# ir.net
KiCad netlist of a schematic drawn in Altium Designer
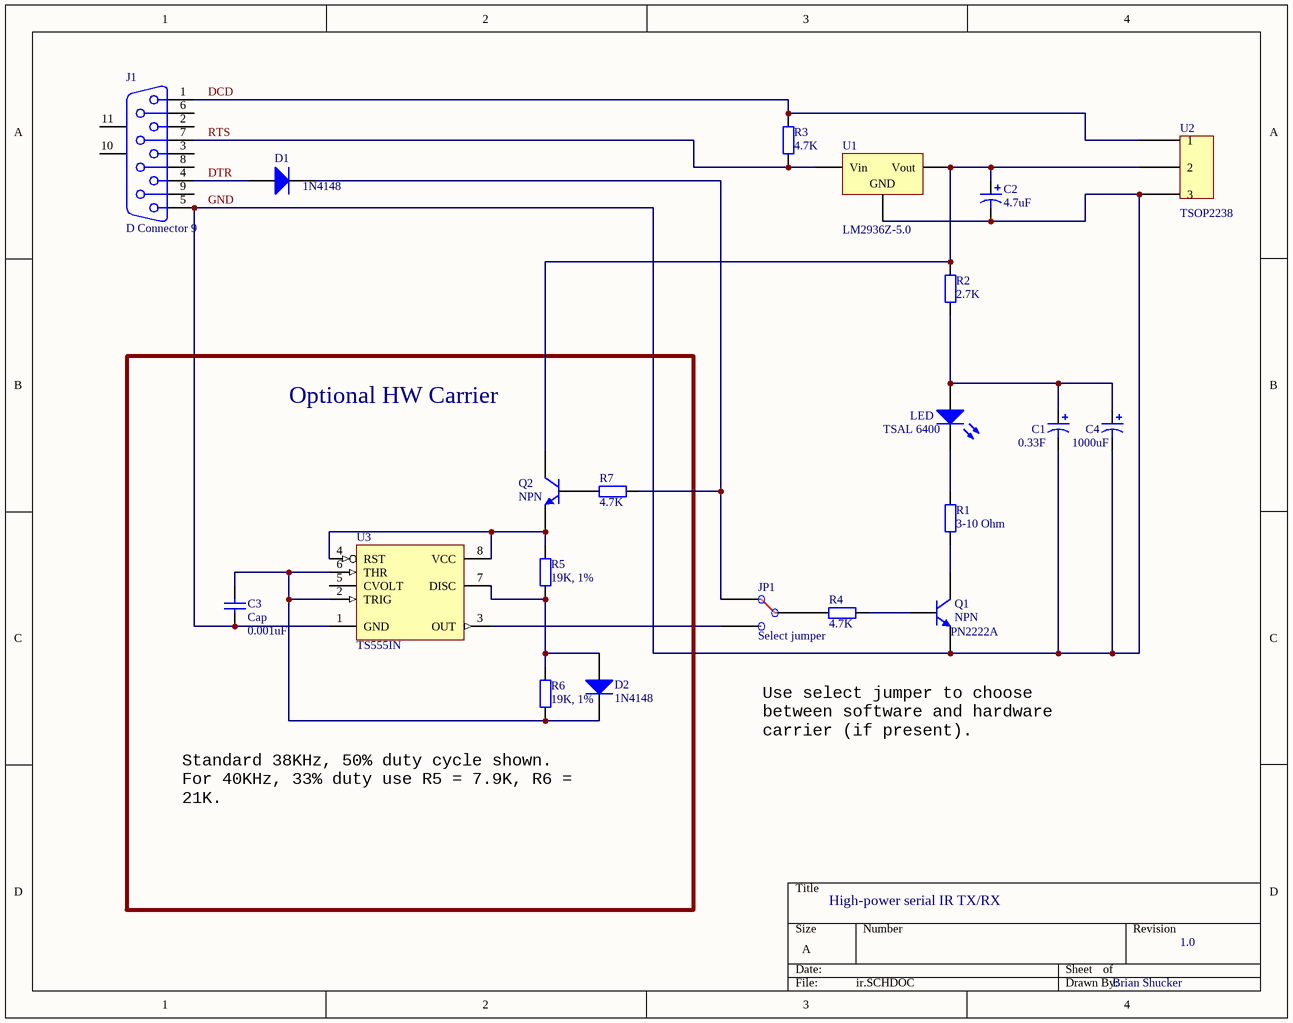
[diagram p0: ir.SCHDOC]

(export (version "E")
  (design (tool "Eeschema 10.0.6"))
  (components
    (comp (ref "C1")
      (value "0.33F")
      (footprint "SuperCapacitor")
      (description "Polarized Capacitor (Radial)")
      (fields (field (name "PUBLISHER") "Altium Limited"))
      (libsource (lib "Miscellaneous Devices") (part "Cap Pol1"))
    )
    (comp (ref "C2")
      (value "4.7uF")
      (footprint "CAPPR1.5-4x5")
      (description "Polarized Capacitor (Radial)")
      (fields (field (name "Comment") "Cap Pol1") (field (name "PUBLISHER") "Altium Limited"))
      (libsource (lib "Miscellaneous Devices") (part "Cap Pol1"))
    )
    (comp (ref "C3")
      (value "Cap")
      (footprint "Axial-0.1")
      (description "Capacitor")
      (fields (field (name "ALTIUM_VALUE") "0.001uF") (field (name "PUBLISHER") "Altium Limited"))
      (libsource (lib "Miscellaneous Devices") (part "Cap"))
    )
    (comp (ref "C4")
      (value "1000uF")
      (footprint "Cap 10mm (5mm lead space)")
      (description "Polarized Capacitor (Radial)")
      (fields (field (name "PUBLISHER") "Altium Limited"))
      (libsource (lib "Miscellaneous Devices") (part "Cap Pol1"))
    )
    (comp (ref "D1")
      (value "1N4148")
      (footprint "DIO7.1-3.9x1.9")
      (description "High Conductance Fast Diode")
      (fields (field (name "PUBLISHER") "Altium Limited"))
      (libsource (lib "Miscellaneous Devices") (part "Diode 1N4148"))
    )
    (comp (ref "D2")
      (value "1N4148")
      (footprint "DIO7.1-3.9x1.9")
      (description "High Conductance Fast Diode")
      (fields (field (name "PUBLISHER") "Altium Limited"))
      (libsource (lib "Miscellaneous Devices") (part "Diode 1N4148"))
    )
    (comp (ref "J1")
      (value "D Connector 9")
      (footprint "DSUB1.385-2H9")
      (description "Receptacle Assembly, 9 Position, Right Angle")
      (fields (field (name "PUBLISHER") "Altium Limited"))
      (libsource (lib "Miscellaneous Connectors") (part "D Connector 9"))
    )
    (comp (ref "JP1")
      (value "Select jumper")
      (footprint "Select Jumper")
      (description "Jumper switch: 1 common, 2 poles")
      (libsource (lib "robo") (part "Select jumper"))
    )
    (comp (ref "LED")
      (value "TSAL 6400")
      (footprint "LED")
      (description "Typical INFRARED GaAs LED")
      (fields (field (name "PUBLISHER") "Altium Limited"))
      (libsource (lib "Miscellaneous Devices") (part "LED0"))
    )
    (comp (ref "Q1")
      (value "NPN")
      (footprint "TO-92")
      (description "NPN Bipolar Transistor")
      (fields (field (name "PUBLISHER") "Altium Limited"))
      (libsource (lib "Miscellaneous Devices") (part "NPN"))
    )
    (comp (ref "Q2")
      (value "NPN")
      (footprint "TO-92")
      (description "NPN Bipolar Transistor")
      (fields (field (name "PUBLISHER") "Altium Limited"))
      (libsource (lib "Miscellaneous Devices") (part "NPN"))
    )
    (comp (ref "R1")
      (value "3-10 Ohm")
      (footprint "AXIAL-0.5")
      (description "Resistor")
      (fields (field (name "PUBLISHER") "Altium Limited"))
      (libsource (lib "") (part "Res2_1"))
    )
    (comp (ref "R2")
      (value "2.7K")
      (footprint "AXIAL-0.4")
      (description "Resistor")
      (fields (field (name "PUBLISHER") "Altium Limited"))
      (libsource (lib "") (part "Res2_1"))
    )
    (comp (ref "R3")
      (value "4.7K")
      (footprint "AXIAL-0.4")
      (description "Resistor")
      (fields (field (name "PUBLISHER") "Altium Limited"))
      (libsource (lib "") (part "Res2_1"))
    )
    (comp (ref "R4")
      (value "4.7K")
      (footprint "AXIAL-0.4")
      (description "Resistor")
      (fields (field (name "Comment") "Res2") (field (name "PUBLISHER") "Altium Limited"))
      (libsource (lib "Miscellaneous Devices") (part "Res2"))
    )
    (comp (ref "R5")
      (value "19K, 1%")
      (footprint "AXIAL-0.4")
      (description "Resistor")
      (fields (field (name "Comment") "Res2") (field (name "PUBLISHER") "Altium Limited"))
      (libsource (lib "") (part "Res2_1"))
    )
    (comp (ref "R6")
      (value "19K, 1%")
      (footprint "AXIAL-0.4")
      (description "Resistor")
      (fields (field (name "Comment") "Res2") (field (name "PUBLISHER") "Altium Limited"))
      (libsource (lib "") (part "Res2_1"))
    )
    (comp (ref "R7")
      (value "4.7K")
      (footprint "AXIAL-0.4")
      (description "Resistor")
      (fields (field (name "Comment") "Res2") (field (name "PUBLISHER") "Altium Limited"))
      (libsource (lib "") (part "Res2_2"))
    )
    (comp (ref "U1")
      (value "LM2936Z-5.0")
      (footprint "TO-92 straight")
      (description "Voltage Regulator")
      (fields (field (name "PUBLISHER") "Altium Limited"))
      (libsource (lib "Miscellaneous Devices") (part "Volt Reg"))
    )
    (comp (ref "U2")
      (value "TSOP2238")
      (footprint "vishay1")
      (libsource (lib "ir") (part "TSOP2238 IR RECEIVER MODULE"))
    )
    (comp (ref "U3")
      (value "TS555IN")
      (footprint "DIP8")
      (description "Low-Power Single CMOS Timer")
      (fields (field (name "PUBLISHER") "Altium Limited"))
      (libsource (lib "ST Analog Timer Circuit") (part "TS555IN"))
    )
  )
  (nets
    (net (code "1") (name "/DCD") (class "Default")
      (node (ref "J1") (pin "1") (pinfunction "1_1") (pintype "passive"))
      (node (ref "R3") (pin "2") (pinfunction "2_2") (pintype "passive"))
      (node (ref "U2") (pin "1") (pinfunction "1_1") (pintype "open_collector"))
    )
    (net (code "2") (name "/DTR") (class "Default")
      (node (ref "D1") (pin "1") (pinfunction "A_1") (pintype "passive"))
      (node (ref "J1") (pin "4") (pinfunction "4_4") (pintype "passive"))
    )
    (net (code "3") (name "/GND") (class "Default")
      (node (ref "C1") (pin "2") (pinfunction "2_2") (pintype "passive"))
      (node (ref "C2") (pin "2") (pinfunction "2_2") (pintype "passive"))
      (node (ref "C3") (pin "1") (pinfunction "1_1") (pintype "passive"))
      (node (ref "C4") (pin "2") (pinfunction "2_2") (pintype "passive"))
      (node (ref "J1") (pin "5") (pinfunction "5_5") (pintype "passive"))
      (node (ref "Q1") (pin "3") (pinfunction "E_3") (pintype "passive"))
      (node (ref "U1") (pin "2") (pinfunction "GND_2") (pintype "passive"))
      (node (ref "U2") (pin "3") (pinfunction "3_3") (pintype "passive"))
      (node (ref "U3") (pin "1") (pinfunction "GND_1") (pintype "power_in"))
    )
    (net (code "4") (name "/RTS") (class "Default")
      (node (ref "J1") (pin "7") (pinfunction "7_7") (pintype "passive"))
      (node (ref "R3") (pin "1") (pinfunction "1_1") (pintype "passive"))
      (node (ref "U1") (pin "1") (pinfunction "Vin_1") (pintype "passive"))
    )
    (net (code "5") (name "Net-(D1-K)") (class "Default")
      (node (ref "D1") (pin "2") (pinfunction "K_2") (pintype "passive"))
      (node (ref "JP1") (pin "1") (pinfunction "1_1") (pintype "passive"))
      (node (ref "R7") (pin "1") (pinfunction "1_1") (pintype "passive"))
    )
    (net (code "6") (name "Net-(D2-A)") (class "Default")
      (node (ref "D2") (pin "1") (pinfunction "A_1") (pintype "passive"))
      (node (ref "R5") (pin "1") (pinfunction "1_1") (pintype "passive"))
      (node (ref "R6") (pin "2") (pinfunction "2_2") (pintype "passive"))
      (node (ref "U3") (pin "7") (pinfunction "DISC_7") (pintype "open_collector"))
    )
    (net (code "7") (name "Net-(D2-K)") (class "Default")
      (node (ref "C3") (pin "2") (pinfunction "2_2") (pintype "passive"))
      (node (ref "D2") (pin "2") (pinfunction "K_2") (pintype "passive"))
      (node (ref "R6") (pin "1") (pinfunction "1_1") (pintype "passive"))
      (node (ref "U3") (pin "2") (pinfunction "TRIG_2") (pintype "input"))
      (node (ref "U3") (pin "6") (pinfunction "THR_6") (pintype "input"))
    )
    (net (code "8") (name "Net-(JP1-Pad2)") (class "Default")
      (node (ref "JP1") (pin "2") (pinfunction "2_2") (pintype "passive"))
      (node (ref "R4") (pin "1") (pinfunction "1_1") (pintype "passive"))
    )
    (net (code "9") (name "Net-(LED-A)") (class "Default")
      (node (ref "C1") (pin "1") (pinfunction "1_1") (pintype "passive"))
      (node (ref "C4") (pin "1") (pinfunction "1_1") (pintype "passive"))
      (node (ref "LED") (pin "1") (pinfunction "A_1") (pintype "passive"))
      (node (ref "R2") (pin "1") (pinfunction "1_1") (pintype "passive"))
    )
    (net (code "10") (name "Net-(LED-K)") (class "Default")
      (node (ref "LED") (pin "2") (pinfunction "K_2") (pintype "passive"))
      (node (ref "R1") (pin "2") (pinfunction "2_2") (pintype "passive"))
    )
    (net (code "11") (name "Net-(Q1-B)") (class "Default")
      (node (ref "Q1") (pin "2") (pinfunction "B_2") (pintype "passive"))
      (node (ref "R4") (pin "2") (pinfunction "2_2") (pintype "passive"))
    )
    (net (code "12") (name "Net-(Q1-C)") (class "Default")
      (node (ref "Q1") (pin "1") (pinfunction "C_1") (pintype "passive"))
      (node (ref "R1") (pin "1") (pinfunction "1_1") (pintype "passive"))
    )
    (net (code "13") (name "Net-(Q2-B)") (class "Default")
      (node (ref "Q2") (pin "2") (pinfunction "B_2") (pintype "passive"))
      (node (ref "R7") (pin "2") (pinfunction "2_2") (pintype "passive"))
    )
    (net (code "14") (name "Net-(Q2-C)") (class "Default")
      (node (ref "C2") (pin "1") (pinfunction "1_1") (pintype "passive"))
      (node (ref "Q2") (pin "1") (pinfunction "C_1") (pintype "passive"))
      (node (ref "R2") (pin "2") (pinfunction "2_2") (pintype "passive"))
      (node (ref "U1") (pin "3") (pinfunction "Vout_3") (pintype "passive"))
      (node (ref "U2") (pin "2") (pinfunction "2_2") (pintype "power_in"))
    )
    (net (code "15") (name "Net-(Q2-E)") (class "Default")
      (node (ref "Q2") (pin "3") (pinfunction "E_3") (pintype "passive"))
      (node (ref "R5") (pin "2") (pinfunction "2_2") (pintype "passive"))
      (node (ref "U3") (pin "4") (pinfunction "RST_4") (pintype "input"))
      (node (ref "U3") (pin "8") (pinfunction "VCC_8") (pintype "power_in"))
    )
    (net (code "16") (name "Net-(U3-OUT)") (class "Default")
      (node (ref "JP1") (pin "3") (pinfunction "3_3") (pintype "passive"))
      (node (ref "U3") (pin "3") (pinfunction "OUT_3") (pintype "output"))
    )
    (net (code "17") (name "unconnected-(J1-MH1-Pad10)") (class "Default")
      (node (ref "J1") (pin "10") (pinfunction "MH1_10") (pintype "passive"))
    )
    (net (code "18") (name "unconnected-(J1-MH2-Pad11)") (class "Default")
      (node (ref "J1") (pin "11") (pinfunction "MH2_11") (pintype "passive"))
    )
    (net (code "19") (name "unconnected-(J1-Pad2)") (class "Default")
      (node (ref "J1") (pin "2") (pinfunction "2_2") (pintype "passive"))
    )
    (net (code "20") (name "unconnected-(J1-Pad3)") (class "Default")
      (node (ref "J1") (pin "3") (pinfunction "3_3") (pintype "passive"))
    )
    (net (code "21") (name "unconnected-(J1-Pad6)") (class "Default")
      (node (ref "J1") (pin "6") (pinfunction "6_6") (pintype "passive"))
    )
    (net (code "22") (name "unconnected-(J1-Pad8)") (class "Default")
      (node (ref "J1") (pin "8") (pinfunction "8_8") (pintype "passive"))
    )
    (net (code "23") (name "unconnected-(J1-Pad9)") (class "Default")
      (node (ref "J1") (pin "9") (pinfunction "9_9") (pintype "passive"))
    )
    (net (code "24") (name "unconnected-(U3-CVOLT-Pad5)") (class "Default")
      (node (ref "U3") (pin "5") (pinfunction "CVOLT_5") (pintype "passive"))
    )
  )
)
